# schaltplan.net
KiCad netlist of a schematic drawn in EAGLE
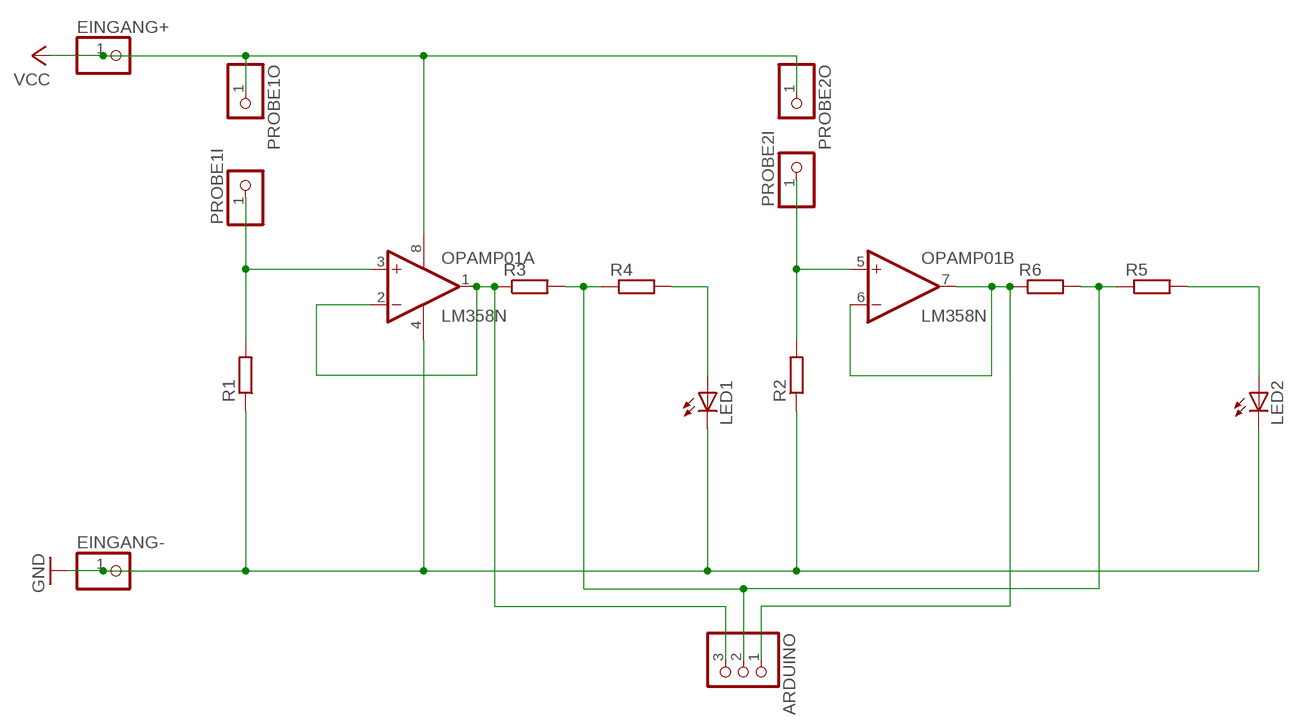
[diagram p0: schematic, sheet 1]

(export (version "E")
  (design (tool "Eeschema 10.0.6"))
  (components
    (comp (ref "ARDUINO")
      (value "PINHD-1X3")
      (footprint "eagle-import:1X03")
      (libsource (lib "eagle-import") (part "PINHD-1X3"))
    )
    (comp (ref "EINGANG+")
      (value "PINHD-1X1")
      (footprint "eagle-import:1X01")
      (libsource (lib "eagle-import") (part "PINHD-1X1"))
    )
    (comp (ref "EINGANG-")
      (value "PINHD-1X1")
      (footprint "eagle-import:1X01")
      (libsource (lib "eagle-import") (part "PINHD-1X1"))
    )
    (comp (ref "LED1")
      (value "LED5MM")
      (footprint "eagle-import:LED5MM")
      (libsource (lib "eagle-import") (part "LED5MM"))
    )
    (comp (ref "LED2")
      (value "LED5MM")
      (footprint "eagle-import:LED5MM")
      (libsource (lib "eagle-import") (part "LED5MM"))
    )
    (comp (ref "OPAMP01")
      (value "LM358N")
      (footprint "eagle-import:DIL08")
      (libsource (lib "eagle-import") (part "LM358N"))
    )
    (comp (ref "PROBE1I")
      (value "PINHD-1X1")
      (footprint "eagle-import:1X01")
      (libsource (lib "eagle-import") (part "PINHD-1X1"))
    )
    (comp (ref "PROBE1O")
      (value "PINHD-1X1")
      (footprint "eagle-import:1X01")
      (libsource (lib "eagle-import") (part "PINHD-1X1"))
    )
    (comp (ref "PROBE2I")
      (value "PINHD-1X1")
      (footprint "eagle-import:1X01")
      (libsource (lib "eagle-import") (part "PINHD-1X1"))
    )
    (comp (ref "PROBE2O")
      (value "PINHD-1X1")
      (footprint "eagle-import:1X01")
      (libsource (lib "eagle-import") (part "PINHD-1X1"))
    )
    (comp (ref "R1")
      (value "R-EU_0207/7")
      (footprint "eagle-import:0207_7")
      (libsource (lib "eagle-import") (part "R-EU_0207/7"))
    )
    (comp (ref "R2")
      (value "R-EU_0207/7")
      (footprint "eagle-import:0207_7")
      (libsource (lib "eagle-import") (part "R-EU_0207/7"))
    )
    (comp (ref "R3")
      (value "R-EU_0207/7")
      (footprint "eagle-import:0207_7")
      (libsource (lib "eagle-import") (part "R-EU_0207/7"))
    )
    (comp (ref "R4")
      (value "R-EU_0207/7")
      (footprint "eagle-import:0207_7")
      (libsource (lib "eagle-import") (part "R-EU_0207/7"))
    )
    (comp (ref "R5")
      (value "R-EU_0207/7")
      (footprint "eagle-import:0207_7")
      (libsource (lib "eagle-import") (part "R-EU_0207/7"))
    )
    (comp (ref "R6")
      (value "R-EU_0207/7")
      (footprint "eagle-import:0207_7")
      (libsource (lib "eagle-import") (part "R-EU_0207/7"))
    )
  )
  (nets
    (net (code "1") (name "GND") (class "Default")
      (node (ref "EINGANG-") (pin "1") (pinfunction "1_1") (pintype "passive"))
      (node (ref "LED1") (pin "K") (pinfunction "C_K") (pintype "passive"))
      (node (ref "LED2") (pin "K") (pinfunction "C_K") (pintype "passive"))
      (node (ref "OPAMP01") (pin "4") (pinfunction "V-_4") (pintype "power_in"))
      (node (ref "R1") (pin "1") (pinfunction "1_1") (pintype "passive"))
      (node (ref "R2") (pin "1") (pinfunction "1_1") (pintype "passive"))
    )
    (net (code "2") (name "Net-(ARDUINO-Pad2)") (class "Default")
      (node (ref "ARDUINO") (pin "2") (pinfunction "2_2") (pintype "passive"))
      (node (ref "R3") (pin "2") (pinfunction "2_2") (pintype "passive"))
      (node (ref "R4") (pin "1") (pinfunction "1_1") (pintype "passive"))
      (node (ref "R5") (pin "1") (pinfunction "1_1") (pintype "passive"))
      (node (ref "R6") (pin "2") (pinfunction "2_2") (pintype "passive"))
    )
    (net (code "3") (name "Net-(LED1-PadA)") (class "Default")
      (node (ref "LED1") (pin "A") (pinfunction "A_A") (pintype "passive"))
      (node (ref "R4") (pin "2") (pinfunction "2_2") (pintype "passive"))
    )
    (net (code "4") (name "Net-(LED2-PadA)") (class "Default")
      (node (ref "LED2") (pin "A") (pinfunction "A_A") (pintype "passive"))
      (node (ref "R5") (pin "2") (pinfunction "2_2") (pintype "passive"))
    )
    (net (code "5") (name "Net-(OPAMP01A-+IN)") (class "Default")
      (node (ref "OPAMP01") (pin "3") (pinfunction "+IN_3") (pintype "input"))
      (node (ref "PROBE1I") (pin "1") (pinfunction "1_1") (pintype "passive"))
      (node (ref "R1") (pin "2") (pinfunction "2_2") (pintype "passive"))
    )
    (net (code "6") (name "Net-(OPAMP01A--IN)") (class "Default")
      (node (ref "ARDUINO") (pin "3") (pinfunction "3_3") (pintype "passive"))
      (node (ref "OPAMP01") (pin "1") (pinfunction "OUT_1") (pintype "output"))
      (node (ref "OPAMP01") (pin "2") (pinfunction "-IN_2") (pintype "input"))
      (node (ref "R3") (pin "1") (pinfunction "1_1") (pintype "passive"))
    )
    (net (code "7") (name "Net-(OPAMP01B-+IN)") (class "Default")
      (node (ref "OPAMP01") (pin "5") (pinfunction "+IN_5") (pintype "input"))
      (node (ref "PROBE2I") (pin "1") (pinfunction "1_1") (pintype "passive"))
      (node (ref "R2") (pin "2") (pinfunction "2_2") (pintype "passive"))
    )
    (net (code "8") (name "Net-(OPAMP01B--IN)") (class "Default")
      (node (ref "ARDUINO") (pin "1") (pinfunction "1_1") (pintype "passive"))
      (node (ref "OPAMP01") (pin "6") (pinfunction "-IN_6") (pintype "input"))
      (node (ref "OPAMP01") (pin "7") (pinfunction "OUT_7") (pintype "output"))
      (node (ref "R6") (pin "1") (pinfunction "1_1") (pintype "passive"))
    )
    (net (code "9") (name "VCC") (class "Default")
      (node (ref "EINGANG+") (pin "1") (pinfunction "1_1") (pintype "passive"))
      (node (ref "OPAMP01") (pin "8") (pinfunction "V+_8") (pintype "power_in"))
      (node (ref "PROBE1O") (pin "1") (pinfunction "1_1") (pintype "passive"))
      (node (ref "PROBE2O") (pin "1") (pinfunction "1_1") (pintype "passive"))
    )
  )
)
